# magnetic_encoder.net
KiCad netlist of a schematic drawn in EAGLE
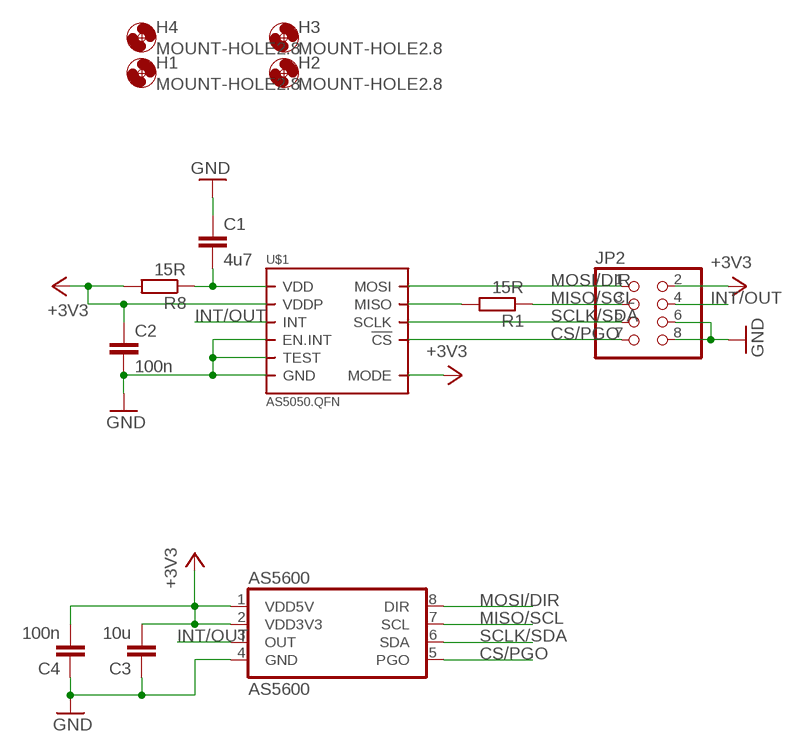
[diagram p0: schematic, sheet 1]

(export (version "E")
  (design (tool "Eeschema 10.0.6"))
  (components
    (comp (ref "AS5600")
      (value "AS5600")
      (footprint "eagle-import:SOIC-8")
      (libsource (lib "eagle-import") (part "AS5600"))
    )
    (comp (ref "C1")
      (value "4u7")
      (footprint "eagle-import:C0603")
      (libsource (lib "eagle-import") (part "C-EUC0603"))
    )
    (comp (ref "C2")
      (value "100n")
      (footprint "eagle-import:C0603")
      (libsource (lib "eagle-import") (part "C-EUC0603"))
    )
    (comp (ref "C3")
      (value "10u")
      (footprint "eagle-import:C0603")
      (libsource (lib "eagle-import") (part "C-EUC0603"))
    )
    (comp (ref "C4")
      (value "100n")
      (footprint "eagle-import:C0603")
      (libsource (lib "eagle-import") (part "C-EUC0603"))
    )
    (comp (ref "H1")
      (value "MOUNT-HOLE2.8")
      (footprint "eagle-import:2,8")
      (libsource (lib "eagle-import") (part "MOUNT-HOLE2.8"))
    )
    (comp (ref "H2")
      (value "MOUNT-HOLE2.8")
      (footprint "eagle-import:2,8")
      (libsource (lib "eagle-import") (part "MOUNT-HOLE2.8"))
    )
    (comp (ref "H3")
      (value "MOUNT-HOLE2.8")
      (footprint "eagle-import:2,8")
      (libsource (lib "eagle-import") (part "MOUNT-HOLE2.8"))
    )
    (comp (ref "H4")
      (value "MOUNT-HOLE2.8")
      (footprint "eagle-import:2,8")
      (libsource (lib "eagle-import") (part "MOUNT-HOLE2.8"))
    )
    (comp (ref "JP2")
      (value "PINHD-2X4")
      (footprint "eagle-import:2X04")
      (libsource (lib "eagle-import") (part "PINHD-2X4"))
    )
    (comp (ref "R1")
      (value "15R")
      (footprint "eagle-import:R0603")
      (libsource (lib "eagle-import") (part "R-EU_R0603"))
    )
    (comp (ref "R8")
      (value "15R")
      (footprint "eagle-import:R0603")
      (libsource (lib "eagle-import") (part "R-EU_R0603"))
    )
    (comp (ref "U$1")
      (value "AS5050.QFN")
      (footprint "eagle-import:QFN.16")
      (libsource (lib "eagle-import") (part "AS5050.QFN"))
    )
  )
  (nets
    (net (code "1") (name "+3V3") (class "Default")
      (node (ref "AS5600") (pin "1") (pinfunction "VDD5V_1") (pintype "power_in"))
      (node (ref "AS5600") (pin "2") (pinfunction "VDD3V3_2") (pintype "power_in"))
      (node (ref "C2") (pin "1") (pinfunction "1_1") (pintype "passive"))
      (node (ref "C3") (pin "2") (pinfunction "2_2") (pintype "passive"))
      (node (ref "C4") (pin "2") (pinfunction "2_2") (pintype "passive"))
      (node (ref "JP2") (pin "2") (pinfunction "2_2") (pintype "passive"))
      (node (ref "R8") (pin "2") (pinfunction "2_2") (pintype "passive"))
      (node (ref "U$1") (pin "11") (pinfunction "VDDP_11") (pintype "bidirectional"))
      (node (ref "U$1") (pin "14") (pinfunction "MODE_14") (pintype "bidirectional"))
    )
    (net (code "2") (name "/CS{slash}PGO") (class "Default")
      (node (ref "AS5600") (pin "5") (pinfunction "PGO_5") (pintype "bidirectional"))
      (node (ref "JP2") (pin "7") (pinfunction "7_7") (pintype "passive"))
      (node (ref "U$1") (pin "4") (pinfunction "~{CS}_4") (pintype "bidirectional"))
    )
    (net (code "3") (name "/INT{slash}OUT") (class "Default")
      (node (ref "AS5600") (pin "3") (pinfunction "OUT_3") (pintype "bidirectional"))
      (node (ref "JP2") (pin "4") (pinfunction "4_4") (pintype "passive"))
      (node (ref "U$1") (pin "15") (pinfunction "INT_15") (pintype "bidirectional"))
    )
    (net (code "4") (name "/MISO{slash}SCL") (class "Default")
      (node (ref "AS5600") (pin "7") (pinfunction "SCL_7") (pintype "bidirectional"))
      (node (ref "JP2") (pin "3") (pinfunction "3_3") (pintype "passive"))
      (node (ref "R1") (pin "1") (pinfunction "1_1") (pintype "passive"))
    )
    (net (code "5") (name "/MOSI{slash}DIR") (class "Default")
      (node (ref "AS5600") (pin "8") (pinfunction "DIR_8") (pintype "bidirectional"))
      (node (ref "JP2") (pin "1") (pinfunction "1_1") (pintype "passive"))
      (node (ref "U$1") (pin "1") (pinfunction "MOSI_1") (pintype "bidirectional"))
    )
    (net (code "6") (name "/SCLK{slash}SDA") (class "Default")
      (node (ref "AS5600") (pin "6") (pinfunction "SDA_6") (pintype "bidirectional"))
      (node (ref "JP2") (pin "5") (pinfunction "5_5") (pintype "passive"))
      (node (ref "U$1") (pin "3") (pinfunction "SCLK_3") (pintype "bidirectional"))
    )
    (net (code "7") (name "GND") (class "Default")
      (node (ref "AS5600") (pin "4") (pinfunction "GND_4") (pintype "power_in"))
      (node (ref "C1") (pin "1") (pinfunction "1_1") (pintype "passive"))
      (node (ref "C2") (pin "2") (pinfunction "2_2") (pintype "passive"))
      (node (ref "C3") (pin "1") (pinfunction "1_1") (pintype "passive"))
      (node (ref "C4") (pin "1") (pinfunction "1_1") (pintype "passive"))
      (node (ref "JP2") (pin "6") (pinfunction "6_6") (pintype "passive"))
      (node (ref "JP2") (pin "8") (pinfunction "8_8") (pintype "passive"))
      (node (ref "U$1") (pin "10") (pinfunction "EN.INT_10") (pintype "bidirectional"))
      (node (ref "U$1") (pin "13") (pinfunction "GND_13") (pintype "bidirectional"))
      (node (ref "U$1") (pin "9") (pinfunction "TEST_9") (pintype "bidirectional"))
    )
    (net (code "8") (name "Net-(U$1-MISO)") (class "Default")
      (node (ref "R1") (pin "2") (pinfunction "2_2") (pintype "passive"))
      (node (ref "U$1") (pin "2") (pinfunction "MISO_2") (pintype "bidirectional"))
    )
    (net (code "9") (name "Net-(U$1-VDD)") (class "Default")
      (node (ref "C1") (pin "2") (pinfunction "2_2") (pintype "passive"))
      (node (ref "R8") (pin "1") (pinfunction "1_1") (pintype "passive"))
      (node (ref "U$1") (pin "12") (pinfunction "VDD_12") (pintype "bidirectional"))
    )
  )
)
